# HandyPico.net
KiCad netlist of a schematic drawn in EasyEDA Pro
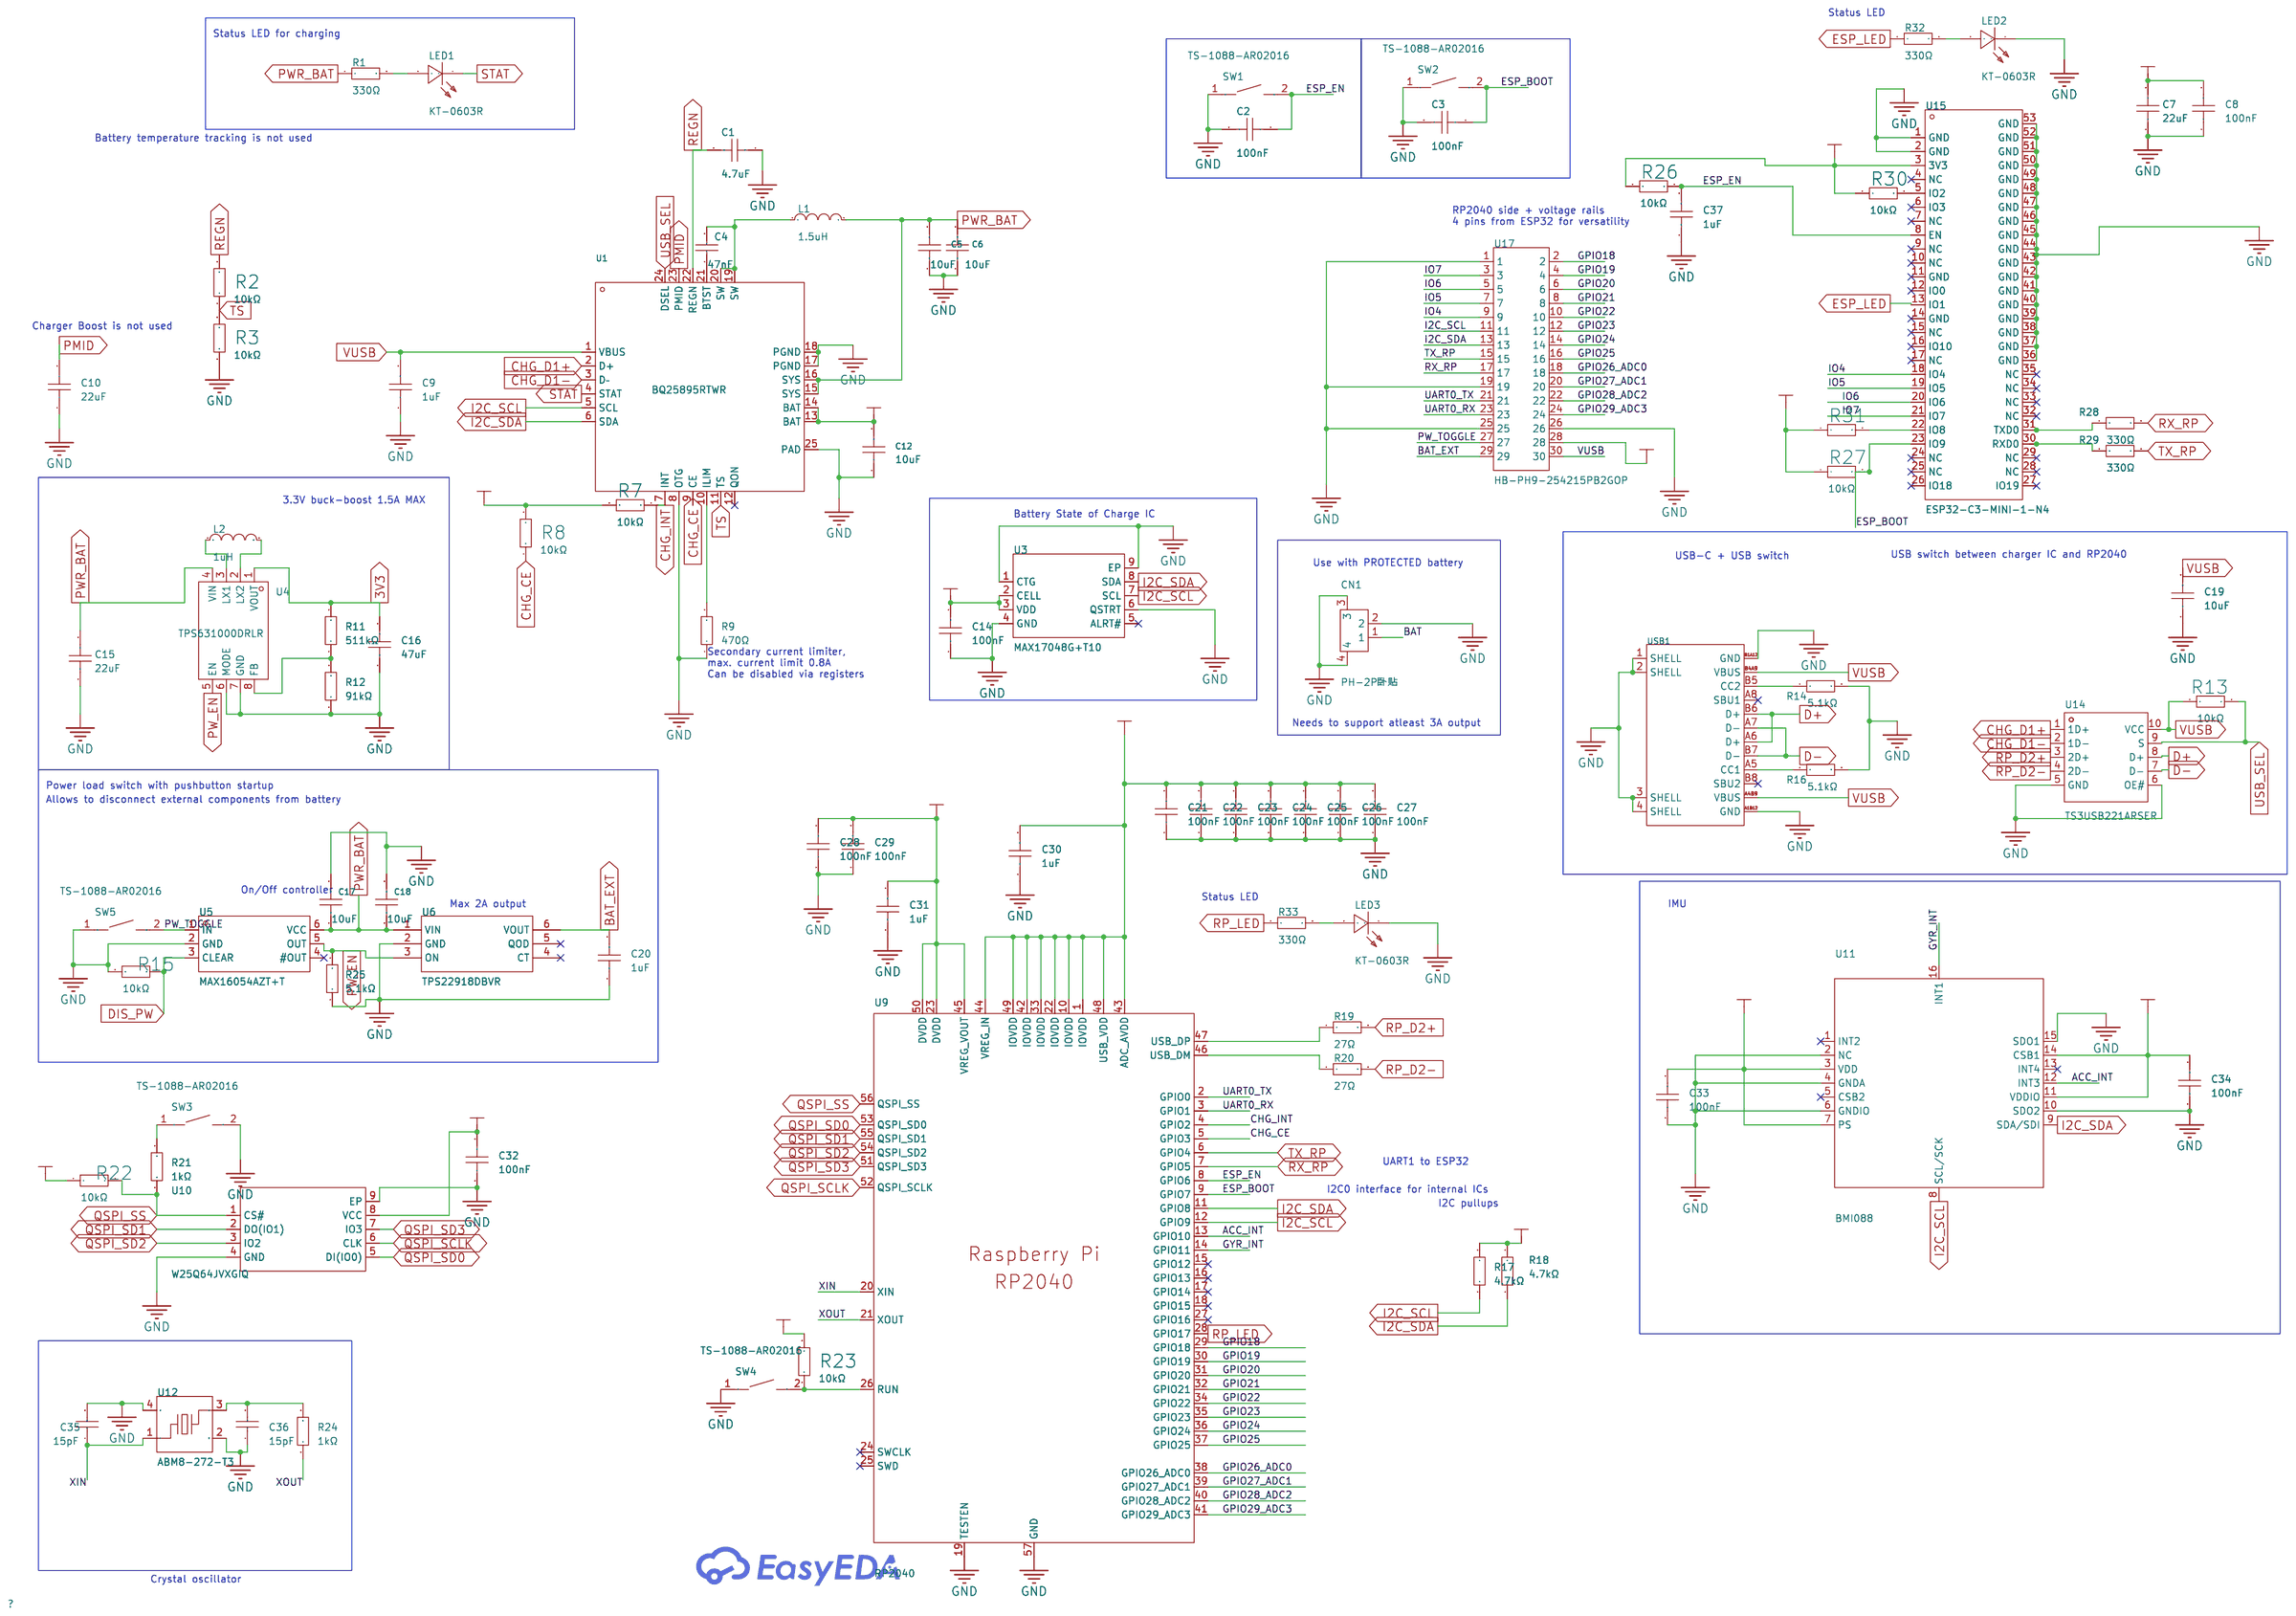
[diagram p0: schematic sheet]

(export (version "E")
  (design (tool "Eeschema 10.0.6"))
  (components
    (comp (ref "C1")
      (value "4.7uF")
      (footprint "easyedapro:C0603")
      (fields
        (field (name "Manufacturer Part") "CL05A475MP5NRNC")
        (field (name "Manufacturer") "SAMSUNG(三星)")
      )
      (libsource (lib "easyedapro") (part "CL10A475KO8NNNC"))
    )
    (comp (ref "C2")
      (value "100nF")
      (footprint "easyedapro:C0603")
      (fields
        (field (name "Manufacturer Part") "CL05B104KO5NNNC")
        (field (name "Manufacturer") "SAMSUNG(三星)")
      )
      (libsource (lib "easyedapro") (part "CC0603KRX7R9BB104"))
    )
    (comp (ref "C3")
      (value "100nF")
      (footprint "easyedapro:C0603")
      (fields
        (field (name "Manufacturer Part") "CL05B104KO5NNNC")
        (field (name "Manufacturer") "SAMSUNG(三星)")
      )
      (libsource (lib "easyedapro") (part "CC0603KRX7R9BB104"))
    )
    (comp (ref "C4")
      (value "47nF")
      (footprint "easyedapro:C0603")
      (fields
        (field (name "Manufacturer Part") "CL10B473KB8NNNC")
        (field (name "Manufacturer") "SAMSUNG(三星)")
      )
      (libsource (lib "easyedapro") (part "CL10B473KB8NNNC"))
    )
    (comp (ref "C5")
      (value "10uF")
      (footprint "easyedapro:C0603")
      (fields
        (field (name "Manufacturer Part") "CL10A106MA8NRNC")
        (field (name "Manufacturer") "SAMSUNG(三星)")
      )
      (libsource (lib "easyedapro") (part "CL10A106MA8NRNC"))
    )
    (comp (ref "C6")
      (value "10uF")
      (footprint "easyedapro:C0603")
      (fields
        (field (name "Manufacturer Part") "CL10A106MA8NRNC")
        (field (name "Manufacturer") "SAMSUNG(三星)")
      )
      (libsource (lib "easyedapro") (part "CL10A106MA8NRNC"))
    )
    (comp (ref "C7")
      (value "22uF")
      (footprint "easyedapro:C0603")
      (fields
        (field (name "Manufacturer Part") "GRM187R61A226ME15D")
        (field (name "Manufacturer") "muRata(村田)")
      )
      (libsource (lib "easyedapro") (part "GRM187R61A226ME15D"))
    )
    (comp (ref "C8")
      (value "100nF")
      (footprint "easyedapro:C0603")
      (fields
        (field (name "Manufacturer Part") "CL05B104KO5NNNC")
        (field (name "Manufacturer") "SAMSUNG(三星)")
      )
      (libsource (lib "easyedapro") (part "CC0603KRX7R9BB104"))
    )
    (comp (ref "C9")
      (value "1uF")
      (footprint "easyedapro:C0603")
      (fields
        (field (name "Manufacturer Part") "CL10A105KB8NNNC")
        (field (name "Manufacturer") "SAMSUNG(三星)")
      )
      (libsource (lib "easyedapro") (part "CL10A105KB8NNNC"))
    )
    (comp (ref "C10")
      (value "22uF")
      (footprint "easyedapro:C0603")
      (fields
        (field (name "Manufacturer Part") "CL10A226MQ8NRNC")
        (field (name "Manufacturer") "SAMSUNG(三星)")
      )
      (libsource (lib "easyedapro") (part "CL10A226MQ8NRNC"))
    )
    (comp (ref "C12")
      (value "10uF")
      (footprint "easyedapro:C0603")
      (fields
        (field (name "Manufacturer Part") "CL10A106MA8NRNC")
        (field (name "Manufacturer") "SAMSUNG(三星)")
      )
      (libsource (lib "easyedapro") (part "CL10A106MA8NRNC"))
    )
    (comp (ref "C14")
      (value "100nF")
      (footprint "easyedapro:C0603")
      (fields
        (field (name "Manufacturer Part") "CL05B104KO5NNNC")
        (field (name "Manufacturer") "SAMSUNG(三星)")
      )
      (libsource (lib "easyedapro") (part "CC0603KRX7R9BB104"))
    )
    (comp (ref "C15")
      (value "22uF")
      (footprint "easyedapro:C0603")
      (fields
        (field (name "Manufacturer Part") "GRM187R61A226ME15D")
        (field (name "Manufacturer") "muRata(村田)")
      )
      (libsource (lib "easyedapro") (part "GRM187R61A226ME15D"))
    )
    (comp (ref "C16")
      (value "47uF")
      (footprint "easyedapro:C0603")
      (fields
        (field (name "Manufacturer Part") "CL10A476MQ8QRNC")
        (field (name "Manufacturer") "SAMSUNG(三星)")
      )
      (libsource (lib "easyedapro") (part "CL10A476MQ8QRNC"))
    )
    (comp (ref "C17")
      (value "10uF")
      (footprint "easyedapro:C0603")
      (fields
        (field (name "Manufacturer Part") "CL10A106MA8NRNC")
        (field (name "Manufacturer") "SAMSUNG(三星)")
      )
      (libsource (lib "easyedapro") (part "CL10A106MA8NRNC"))
    )
    (comp (ref "C18")
      (value "10uF")
      (footprint "easyedapro:C0603")
      (fields
        (field (name "Manufacturer Part") "CL10A106MA8NRNC")
        (field (name "Manufacturer") "SAMSUNG(三星)")
      )
      (libsource (lib "easyedapro") (part "CL10A106MA8NRNC"))
    )
    (comp (ref "C19")
      (value "10uF")
      (footprint "easyedapro:C0603")
      (fields
        (field (name "Manufacturer Part") "CL10A106KP8NNNC")
        (field (name "Manufacturer") "SAMSUNG(三星)")
      )
      (libsource (lib "easyedapro") (part "CL10A106KP8NNNC"))
    )
    (comp (ref "C20")
      (value "1uF")
      (footprint "easyedapro:C0603")
      (fields
        (field (name "Manufacturer Part") "CL10A105KB8NNNC")
        (field (name "Manufacturer") "SAMSUNG(三星)")
      )
      (libsource (lib "easyedapro") (part "CL10A105KB8NNNC"))
    )
    (comp (ref "C21")
      (value "100nF")
      (footprint "easyedapro:C0603")
      (fields
        (field (name "Manufacturer Part") "CL05B104KO5NNNC")
        (field (name "Manufacturer") "SAMSUNG(三星)")
      )
      (libsource (lib "easyedapro") (part "CC0603KRX7R9BB104"))
    )
    (comp (ref "C22")
      (value "100nF")
      (footprint "easyedapro:C0603")
      (fields
        (field (name "Manufacturer Part") "CL05B104KO5NNNC")
        (field (name "Manufacturer") "SAMSUNG(三星)")
      )
      (libsource (lib "easyedapro") (part "CC0603KRX7R9BB104"))
    )
    (comp (ref "C23")
      (value "100nF")
      (footprint "easyedapro:C0603")
      (fields
        (field (name "Manufacturer Part") "CL05B104KO5NNNC")
        (field (name "Manufacturer") "SAMSUNG(三星)")
      )
      (libsource (lib "easyedapro") (part "CC0603KRX7R9BB104"))
    )
    (comp (ref "C24")
      (value "100nF")
      (footprint "easyedapro:C0603")
      (fields
        (field (name "Manufacturer Part") "CL05B104KO5NNNC")
        (field (name "Manufacturer") "SAMSUNG(三星)")
      )
      (libsource (lib "easyedapro") (part "CC0603KRX7R9BB104"))
    )
    (comp (ref "C25")
      (value "100nF")
      (footprint "easyedapro:C0603")
      (fields
        (field (name "Manufacturer Part") "CL05B104KO5NNNC")
        (field (name "Manufacturer") "SAMSUNG(三星)")
      )
      (libsource (lib "easyedapro") (part "CC0603KRX7R9BB104"))
    )
    (comp (ref "C26")
      (value "100nF")
      (footprint "easyedapro:C0603")
      (fields
        (field (name "Manufacturer Part") "CL05B104KO5NNNC")
        (field (name "Manufacturer") "SAMSUNG(三星)")
      )
      (libsource (lib "easyedapro") (part "CC0603KRX7R9BB104"))
    )
    (comp (ref "C27")
      (value "100nF")
      (footprint "easyedapro:C0603")
      (fields
        (field (name "Manufacturer Part") "CL05B104KO5NNNC")
        (field (name "Manufacturer") "SAMSUNG(三星)")
      )
      (libsource (lib "easyedapro") (part "CC0603KRX7R9BB104"))
    )
    (comp (ref "C28")
      (value "100nF")
      (footprint "easyedapro:C0603")
      (fields
        (field (name "Manufacturer Part") "CL05B104KO5NNNC")
        (field (name "Manufacturer") "SAMSUNG(三星)")
      )
      (libsource (lib "easyedapro") (part "CC0603KRX7R9BB104"))
    )
    (comp (ref "C29")
      (value "100nF")
      (footprint "easyedapro:C0603")
      (fields
        (field (name "Manufacturer Part") "CL05B104KO5NNNC")
        (field (name "Manufacturer") "SAMSUNG(三星)")
      )
      (libsource (lib "easyedapro") (part "CC0603KRX7R9BB104"))
    )
    (comp (ref "C30")
      (value "1uF")
      (footprint "easyedapro:C0603")
      (description "Capacitance:1uF Tolerance:±10% Tolerance:±10% Voltage Rating:25V Temperature Coefficient:X5R")
      (fields
        (field (name "Manufacturer Part") "CL05A105KA5NQNC")
        (field (name "Manufacturer") "SAMSUNG(三星)")
      )
      (libsource (lib "easyedapro") (part "CL10A105KB8NNNC"))
    )
    (comp (ref "C31")
      (value "1uF")
      (footprint "easyedapro:C0603")
      (description "Capacitance:1uF Tolerance:±10% Tolerance:±10% Voltage Rating:25V Temperature Coefficient:X5R")
      (fields
        (field (name "Manufacturer Part") "CL05A105KA5NQNC")
        (field (name "Manufacturer") "SAMSUNG(三星)")
      )
      (libsource (lib "easyedapro") (part "CL10A105KB8NNNC"))
    )
    (comp (ref "C32")
      (value "100nF")
      (footprint "easyedapro:C0603")
      (fields
        (field (name "Manufacturer Part") "CL05B104KO5NNNC")
        (field (name "Manufacturer") "SAMSUNG(三星)")
      )
      (libsource (lib "easyedapro") (part "CC0603KRX7R9BB104"))
    )
    (comp (ref "C33")
      (value "100nF")
      (footprint "easyedapro:C0603")
      (fields
        (field (name "Manufacturer Part") "CL05B104KO5NNNC")
        (field (name "Manufacturer") "SAMSUNG(三星)")
      )
      (libsource (lib "easyedapro") (part "CC0603KRX7R9BB104"))
    )
    (comp (ref "C34")
      (value "100nF")
      (footprint "easyedapro:C0603")
      (fields
        (field (name "Manufacturer Part") "CL05B104KO5NNNC")
        (field (name "Manufacturer") "SAMSUNG(三星)")
      )
      (libsource (lib "easyedapro") (part "CC0603KRX7R9BB104"))
    )
    (comp (ref "C35")
      (value "15pF")
      (footprint "easyedapro:C0603")
      (fields
        (field (name "Manufacturer Part") "CL10C150JB8NNNC")
        (field (name "Manufacturer") "SAMSUNG(三星)")
      )
      (libsource (lib "easyedapro") (part "CL10C150JB8NNNC"))
    )
    (comp (ref "C36")
      (value "15pF")
      (footprint "easyedapro:C0603")
      (fields
        (field (name "Manufacturer Part") "CL10C150JB8NNNC")
        (field (name "Manufacturer") "SAMSUNG(三星)")
      )
      (libsource (lib "easyedapro") (part "CL10C150JB8NNNC"))
    )
    (comp (ref "C37")
      (value "1uF")
      (footprint "easyedapro:C0603")
      (description "Capacitance:1uF Tolerance:±10% Tolerance:±10% Voltage Rating:25V Temperature Coefficient:X5R")
      (fields
        (field (name "Manufacturer Part") "CL05A105KA5NQNC")
        (field (name "Manufacturer") "SAMSUNG(三星)")
      )
      (libsource (lib "easyedapro") (part "CL10A105KB8NNNC"))
    )
    (comp (ref "CN1")
      (value "PH-2P卧贴")
      (footprint "easyedapro:CONN-SMD_2P-P2.00_PH2.0-SPWB")
      (fields (field (name "Manufacturer") "BOOMELE(博穆精密)"))
      (libsource (lib "easyedapro") (part "PH2.0-2PWB"))
    )
    (comp (ref "L1")
      (value "1.5uH")
      (footprint "easyedapro:IND-SMD_L4.4-W4.2")
      (fields (field (name "Manufacturer Part") "FXL0420-1R5-M") (field (name "Manufacturer") "cjiang(长江微电)"))
      (libsource (lib "easyedapro") (part "FXL0420-1R5-M"))
    )
    (comp (ref "L2")
      (value "1uH")
      (footprint "easyedapro:L1008")
      (fields
        (field (name "Manufacturer Part") "DFE252012P-1R0M=P2")
        (field (name "Manufacturer") "muRata(村田)")
      )
      (libsource (lib "easyedapro") (part "DFE252012P-1R0M=P2"))
    )
    (comp (ref "LED1")
      (value "KT-0603R")
      (footprint "easyedapro:LED0603-RD")
      (fields (field (name "Manufacturer") "KENTO"))
      (libsource (lib "easyedapro") (part "KT-0603R"))
    )
    (comp (ref "LED2")
      (value "KT-0603R")
      (footprint "easyedapro:LED0603-RD")
      (fields (field (name "Manufacturer") "KENTO"))
      (libsource (lib "easyedapro") (part "KT-0603R"))
    )
    (comp (ref "LED3")
      (value "KT-0603R")
      (footprint "easyedapro:LED0603-RD")
      (fields (field (name "Manufacturer") "KENTO"))
      (libsource (lib "easyedapro") (part "KT-0603R"))
    )
    (comp (ref "R1")
      (value "330Ω")
      (footprint "easyedapro:R0603")
      (fields
        (field (name "Manufacturer Part") "0402WGF3300TCE")
        (field (name "Manufacturer") "UNI-ROYAL(厚声)")
      )
      (libsource (lib "easyedapro") (part "0603WAF2201T5E"))
    )
    (comp (ref "R2")
      (value "10kΩ")
      (footprint "easyedapro:R0603")
      (fields
        (field (name "Manufacturer Part") "0402WGF1002TCE")
        (field (name "Manufacturer") "UNI-ROYAL(厚声)")
      )
      (libsource (lib "easyedapro") (part "0603WAF1002T5E"))
    )
    (comp (ref "R3")
      (value "10kΩ")
      (footprint "easyedapro:R0603")
      (fields
        (field (name "Manufacturer Part") "0402WGF1002TCE")
        (field (name "Manufacturer") "UNI-ROYAL(厚声)")
      )
      (libsource (lib "easyedapro") (part "0603WAF1002T5E"))
    )
    (comp (ref "R7")
      (value "10kΩ")
      (footprint "easyedapro:R0603")
      (fields
        (field (name "Manufacturer Part") "0402WGF1002TCE")
        (field (name "Manufacturer") "UNI-ROYAL(厚声)")
      )
      (libsource (lib "easyedapro") (part "0603WAF1002T5E"))
    )
    (comp (ref "R8")
      (value "10kΩ")
      (footprint "easyedapro:R0603")
      (fields
        (field (name "Manufacturer Part") "0402WGF1002TCE")
        (field (name "Manufacturer") "UNI-ROYAL(厚声)")
      )
      (libsource (lib "easyedapro") (part "0603WAF1002T5E"))
    )
    (comp (ref "R9")
      (value "470Ω")
      (footprint "easyedapro:R0603")
      (fields
        (field (name "Manufacturer Part") "0402WGF4700TCE")
        (field (name "Manufacturer") "UNI-ROYAL(厚声)")
      )
      (libsource (lib "easyedapro") (part "0603WAF4700T5E"))
    )
    (comp (ref "R11")
      (value "511kΩ")
      (footprint "easyedapro:R0603")
      (fields
        (field (name "Manufacturer Part") "0402WGF5113TCE")
        (field (name "Manufacturer") "UNI-ROYAL(厚声)")
      )
      (libsource (lib "easyedapro") (part "0603WAF5113T5E"))
    )
    (comp (ref "R12")
      (value "91kΩ")
      (footprint "easyedapro:R0603")
      (fields
        (field (name "Manufacturer Part") "0402WGF9102TCE")
        (field (name "Manufacturer") "UNI-ROYAL(厚声)")
      )
      (libsource (lib "easyedapro") (part "0603WAF9102T5E"))
    )
    (comp (ref "R13")
      (value "10kΩ")
      (footprint "easyedapro:R0603")
      (fields
        (field (name "Manufacturer Part") "0402WGF1002TCE")
        (field (name "Manufacturer") "UNI-ROYAL(厚声)")
      )
      (libsource (lib "easyedapro") (part "0603WAF1002T5E"))
    )
    (comp (ref "R14")
      (value "5.1kΩ")
      (footprint "easyedapro:R0603")
      (fields
        (field (name "Manufacturer Part") "0402WGF5101TCE")
        (field (name "Manufacturer") "UNI-ROYAL(厚声)")
      )
      (libsource (lib "easyedapro") (part "0603WAF5101T5E"))
    )
    (comp (ref "R15")
      (value "10kΩ")
      (footprint "easyedapro:R0603")
      (fields
        (field (name "Manufacturer Part") "0402WGF1002TCE")
        (field (name "Manufacturer") "UNI-ROYAL(厚声)")
      )
      (libsource (lib "easyedapro") (part "0603WAF1002T5E"))
    )
    (comp (ref "R16")
      (value "5.1kΩ")
      (footprint "easyedapro:R0603")
      (fields
        (field (name "Manufacturer Part") "0402WGF5101TCE")
        (field (name "Manufacturer") "UNI-ROYAL(厚声)")
      )
      (libsource (lib "easyedapro") (part "0603WAF5101T5E"))
    )
    (comp (ref "R17")
      (value "4.7kΩ")
      (footprint "easyedapro:R0603")
      (fields
        (field (name "Manufacturer Part") "0402WGF4701TCE")
        (field (name "Manufacturer") "UNI-ROYAL(厚声)")
      )
      (libsource (lib "easyedapro") (part "0603WAF4701T5E"))
    )
    (comp (ref "R18")
      (value "4.7kΩ")
      (footprint "easyedapro:R0603")
      (fields
        (field (name "Manufacturer Part") "0402WGF4701TCE")
        (field (name "Manufacturer") "UNI-ROYAL(厚声)")
      )
      (libsource (lib "easyedapro") (part "0603WAF4701T5E"))
    )
    (comp (ref "R19")
      (value "27Ω")
      (footprint "easyedapro:R0603")
      (fields
        (field (name "Manufacturer Part") "0603WAF270JT5E")
        (field (name "Manufacturer") "UNI-ROYAL(厚声)")
      )
      (libsource (lib "easyedapro") (part "0603WAF270JT5E"))
    )
    (comp (ref "R20")
      (value "27Ω")
      (footprint "easyedapro:R0603")
      (fields
        (field (name "Manufacturer Part") "0603WAF270JT5E")
        (field (name "Manufacturer") "UNI-ROYAL(厚声)")
      )
      (libsource (lib "easyedapro") (part "0603WAF270JT5E"))
    )
    (comp (ref "R21")
      (value "1kΩ")
      (footprint "easyedapro:R0603")
      (fields
        (field (name "Manufacturer Part") "0402WGF1001TCE")
        (field (name "Manufacturer") "UNI-ROYAL(厚声)")
      )
      (libsource (lib "easyedapro") (part "0603WAF1001T5E"))
    )
    (comp (ref "R22")
      (value "10kΩ")
      (footprint "easyedapro:R0603")
      (fields
        (field (name "Manufacturer Part") "0402WGF1002TCE")
        (field (name "Manufacturer") "UNI-ROYAL(厚声)")
      )
      (libsource (lib "easyedapro") (part "0603WAF1002T5E"))
    )
    (comp (ref "R23")
      (value "10kΩ")
      (footprint "easyedapro:R0603")
      (fields
        (field (name "Manufacturer Part") "0402WGF1002TCE")
        (field (name "Manufacturer") "UNI-ROYAL(厚声)")
      )
      (libsource (lib "easyedapro") (part "0603WAF1002T5E"))
    )
    (comp (ref "R24")
      (value "1kΩ")
      (footprint "easyedapro:R0603")
      (fields
        (field (name "Manufacturer Part") "0402WGF1001TCE")
        (field (name "Manufacturer") "UNI-ROYAL(厚声)")
      )
      (libsource (lib "easyedapro") (part "0603WAF1001T5E"))
    )
    (comp (ref "R25")
      (value "5.1kΩ")
      (footprint "easyedapro:R0603")
      (fields
        (field (name "Manufacturer Part") "0402WGF5101TCE")
        (field (name "Manufacturer") "UNI-ROYAL(厚声)")
      )
      (libsource (lib "easyedapro") (part "0603WAF5101T5E"))
    )
    (comp (ref "R26")
      (value "10kΩ")
      (footprint "easyedapro:R0603")
      (fields
        (field (name "Manufacturer Part") "0402WGF1002TCE")
        (field (name "Manufacturer") "UNI-ROYAL(厚声)")
      )
      (libsource (lib "easyedapro") (part "0603WAF1002T5E"))
    )
    (comp (ref "R27")
      (value "10kΩ")
      (footprint "easyedapro:R0603")
      (fields
        (field (name "Manufacturer Part") "0402WGF1002TCE")
        (field (name "Manufacturer") "UNI-ROYAL(厚声)")
      )
      (libsource (lib "easyedapro") (part "0603WAF1002T5E"))
    )
    (comp (ref "R28")
      (value "330Ω")
      (footprint "easyedapro:R0603")
      (fields
        (field (name "Manufacturer Part") "0402WGF3300TCE")
        (field (name "Manufacturer") "UNI-ROYAL(厚声)")
      )
      (libsource (lib "easyedapro") (part "0603WAF3300T5E"))
    )
    (comp (ref "R29")
      (value "330Ω")
      (footprint "easyedapro:R0603")
      (fields
        (field (name "Manufacturer Part") "0402WGF3300TCE")
        (field (name "Manufacturer") "UNI-ROYAL(厚声)")
      )
      (libsource (lib "easyedapro") (part "0603WAF3300T5E"))
    )
    (comp (ref "R30")
      (value "10kΩ")
      (footprint "easyedapro:R0603")
      (fields
        (field (name "Manufacturer Part") "0402WGF1002TCE")
        (field (name "Manufacturer") "UNI-ROYAL(厚声)")
      )
      (libsource (lib "easyedapro") (part "0603WAF1002T5E"))
    )
    (comp (ref "R31")
      (value "10kΩ")
      (footprint "easyedapro:R0603")
      (fields
        (field (name "Manufacturer Part") "0402WGF1002TCE")
        (field (name "Manufacturer") "UNI-ROYAL(厚声)")
      )
      (libsource (lib "easyedapro") (part "0603WAF1002T5E"))
    )
    (comp (ref "R32")
      (value "330Ω")
      (footprint "easyedapro:R0603")
      (fields
        (field (name "Manufacturer Part") "0402WGF3300TCE")
        (field (name "Manufacturer") "UNI-ROYAL(厚声)")
      )
      (libsource (lib "easyedapro") (part "0603WAF2201T5E"))
    )
    (comp (ref "R33")
      (value "330Ω")
      (footprint "easyedapro:R0603")
      (fields
        (field (name "Manufacturer Part") "0402WGF3300TCE")
        (field (name "Manufacturer") "UNI-ROYAL(厚声)")
      )
      (libsource (lib "easyedapro") (part "0603WAF2201T5E"))
    )
    (comp (ref "SW1")
      (value "TS-1088-AR02016")
      (footprint "easyedapro:SW-SMD_L3.9-W3.0-P4.45")
      (fields (field (name "Manufacturer") "XUNPU(讯普)"))
      (libsource (lib "easyedapro") (part "TS-1088-AR02016"))
    )
    (comp (ref "SW2")
      (value "TS-1088-AR02016")
      (footprint "easyedapro:SW-SMD_L3.9-W3.0-P4.45")
      (fields (field (name "Manufacturer") "XUNPU(讯普)"))
      (libsource (lib "easyedapro") (part "TS-1088-AR02016"))
    )
    (comp (ref "SW3")
      (value "TS-1088-AR02016")
      (footprint "easyedapro:SW-SMD_L3.9-W3.0-P4.45")
      (fields (field (name "Manufacturer") "XUNPU(讯普)"))
      (libsource (lib "easyedapro") (part "TS-1088-AR02016"))
    )
    (comp (ref "SW4")
      (value "TS-1088-AR02016")
      (footprint "easyedapro:SW-SMD_L3.9-W3.0-P4.45")
      (fields (field (name "Manufacturer") "XUNPU(讯普)"))
      (libsource (lib "easyedapro") (part "TS-1088-AR02016"))
    )
    (comp (ref "SW5")
      (value "TS-1088-AR02016")
      (footprint "easyedapro:SW-SMD_L3.9-W3.0-P4.45")
      (fields (field (name "Manufacturer") "XUNPU(讯普)"))
      (libsource (lib "easyedapro") (part "TS-1088-AR02016"))
    )
    (comp (ref "U1")
      (value "BQ25895RTWR")
      (footprint "easyedapro:QFN-24_L4.0-W4.0-P0.50-TL-EP2.7")
      (fields (field (name "Manufacturer") "TI(德州仪器)"))
      (libsource (lib "easyedapro") (part "BQ25895RTWR"))
    )
    (comp (ref "U3")
      (value "MAX17048G+T10")
      (footprint "easyedapro:TDFN-8_L2.0-W2.0-P0.50-BL-EP1.2")
      (fields (field (name "Manufacturer") "ADI(亚德诺)/MAXIM(美信)"))
      (libsource (lib "easyedapro") (part "MAX17048G+T10"))
    )
    (comp (ref "U4")
      (value "TPS631000DRLR")
      (footprint "easyedapro:SOT-583-8_L2.1-W1.2-P0.50-LS1.6-BL")
      (fields (field (name "Manufacturer") "TI(德州仪器)"))
      (libsource (lib "easyedapro") (part "TPS631000DRLR"))
    )
    (comp (ref "U5")
      (value "MAX16054AZT+T")
      (footprint "easyedapro:TSOT-23-6_L2.9-W1.6-P0.95-LS2.8-TL")
      (fields (field (name "Manufacturer") "ADI(亚德诺)"))
      (libsource (lib "easyedapro") (part "MAX16054AZT+T"))
    )
    (comp (ref "U6")
      (value "TPS22918DBVR")
      (footprint "easyedapro:SOT-23-6_L2.9-W1.6-P0.95-LS2.8-BR")
      (fields (field (name "Manufacturer") "TI(德州仪器)"))
      (libsource (lib "easyedapro") (part "TPS22918DBVR"))
    )
    (comp (ref "U9")
      (value "RP2040")
      (footprint "easyedapro:LQFN-56_L7.0-W7.0-P0.4-EP")
      (description "CPU Core:- CPU Maximum Speed:133MHz Number of I/O:30 ADC (Bit):12bit Applications:-")
      (fields (field (name "Manufacturer") "Raspberry Pi(树莓派)"))
      (libsource (lib "easyedapro") (part "RP2040"))
    )
    (comp (ref "U10")
      (value "W25Q64JVXGIQ")
      (footprint "easyedapro:XSON-8_L4.0-W4.0-P0.80-TL-EP")
      (fields (field (name "Manufacturer") "Winbond(华邦)"))
      (libsource (lib "easyedapro") (part "W25Q64JVXGIQ"))
    )
    (comp (ref "U11")
      (value "BMI088")
      (footprint "easyedapro:LGA-16_L4.5-W3.0-P0.50-BL")
      (description "Sensor Type:加速度计陀螺仪 Operating Temperature:-40°C~+85°C Operating Temperature:-40°C~+85°C")
      (fields (field (name "Manufacturer") "Bosch(博世)"))
      (libsource (lib "easyedapro") (part "BMI088"))
    )
    (comp (ref "U12")
      (value "ABM8-272-T3")
      (footprint "easyedapro:CRYSTAL-SMD_4P-L3.2-W2.5-BL")
      (fields (field (name "Manufacturer") "ABRACON"))
      (libsource (lib "easyedapro") (part "ABM8-272-T3_C20625731"))
    )
    (comp (ref "U14")
      (value "TS3USB221ARSER")
      (footprint "easyedapro:UQFN-10_L2.0-W1.5-P0.50-BL")
      (fields (field (name "Manufacturer") "TI(德州仪器)"))
      (libsource (lib "easyedapro") (part "TS3USB221ARSER"))
    )
    (comp (ref "U15")
      (value "ESP32-C3-MINI-1-N4")
      (footprint "easyedapro:WIFIM-SMD_ESP32-C3-MINI-1")
      (fields (field (name "Manufacturer") "ESPRESSIF(乐鑫)"))
      (libsource (lib "easyedapro") (part "ESP32-C3-MINI-1-N4"))
    )
    (comp (ref "U17")
      (value "HB-PH9-254215PB2GOP")
      (footprint "easyedapro:HDR-SMD_30P-P2.54-V-M-R2-C15-S7.4")
      (fields (field (name "Manufacturer") "HANBO(汉博)"))
      (libsource (lib "easyedapro") (part "HB-PH9-254215PB2GOP"))
    )
    (comp (ref "USB1")
      (value "HC-TYPE-C-16P-01A-R")
      (footprint "easyedapro:USB-C-SMD_G-SWITCH_GT-USB-7010EN")
      (fields (field (name "Manufacturer") "HCTL(华灿天禄)"))
      (libsource (lib "easyedapro") (part "HC-TYPE-C-16P-01A-R"))
    )
  )
  (nets
    (net (code "1") (name "/ACC_INT") (class "Default")
      (node (ref "U11") (pin "12") (pinfunction "INT3_12") (pintype "unspecified"))
      (node (ref "U9") (pin "13") (pinfunction "GPIO10_13") (pintype "bidirectional"))
    )
    (net (code "2") (name "/ESP_BOOT") (class "Default")
      (node (ref "C3") (pin "1") (pinfunction "1_1") (pintype "unspecified"))
      (node (ref "R27") (pin "2") (pinfunction "2_2") (pintype "input"))
      (node (ref "SW2") (pin "2") (pinfunction "2_2") (pintype "unspecified"))
      (node (ref "U15") (pin "23") (pinfunction "IO9_23") (pintype "unspecified"))
      (node (ref "U9") (pin "9") (pinfunction "GPIO7_9") (pintype "bidirectional"))
    )
    (net (code "3") (name "/ESP_EN") (class "Default")
      (node (ref "C2") (pin "1") (pinfunction "1_1") (pintype "unspecified"))
      (node (ref "C37") (pin "2") (pinfunction "2_2") (pintype "unspecified"))
      (node (ref "R26") (pin "1") (pinfunction "1_1") (pintype "input"))
      (node (ref "SW1") (pin "2") (pinfunction "2_2") (pintype "unspecified"))
      (node (ref "U15") (pin "8") (pinfunction "EN_8") (pintype "unspecified"))
      (node (ref "U9") (pin "8") (pinfunction "GPIO6_8") (pintype "bidirectional"))
    )
    (net (code "4") (name "/GPIO18") (class "Default")
      (node (ref "U17") (pin "2") (pinfunction "2_2") (pintype "unspecified"))
      (node (ref "U9") (pin "29") (pinfunction "GPIO18_29") (pintype "bidirectional"))
    )
    (net (code "5") (name "/GPIO19") (class "Default")
      (node (ref "U17") (pin "4") (pinfunction "4_4") (pintype "unspecified"))
      (node (ref "U9") (pin "30") (pinfunction "GPIO19_30") (pintype "bidirectional"))
    )
    (net (code "6") (name "/GPIO20") (class "Default")
      (node (ref "U17") (pin "6") (pinfunction "6_6") (pintype "unspecified"))
      (node (ref "U9") (pin "31") (pinfunction "GPIO20_31") (pintype "bidirectional"))
    )
    (net (code "7") (name "/GPIO21") (class "Default")
      (node (ref "U17") (pin "8") (pinfunction "8_8") (pintype "unspecified"))
      (node (ref "U9") (pin "32") (pinfunction "GPIO21_32") (pintype "bidirectional"))
    )
    (net (code "8") (name "/GPIO22") (class "Default")
      (node (ref "U17") (pin "10") (pinfunction "10_10") (pintype "unspecified"))
      (node (ref "U9") (pin "34") (pinfunction "GPIO22_34") (pintype "bidirectional"))
    )
    (net (code "9") (name "/GPIO23") (class "Default")
      (node (ref "U17") (pin "12") (pinfunction "12_12") (pintype "unspecified"))
      (node (ref "U9") (pin "35") (pinfunction "GPIO23_35") (pintype "bidirectional"))
    )
    (net (code "10") (name "/GPIO24") (class "Default")
      (node (ref "U17") (pin "14") (pinfunction "14_14") (pintype "unspecified"))
      (node (ref "U9") (pin "36") (pinfunction "GPIO24_36") (pintype "bidirectional"))
    )
    (net (code "11") (name "/GPIO25") (class "Default")
      (node (ref "U17") (pin "16") (pinfunction "16_16") (pintype "unspecified"))
      (node (ref "U9") (pin "37") (pinfunction "GPIO25_37") (pintype "bidirectional"))
    )
    (net (code "12") (name "/GPIO26_ADC0") (class "Default")
      (node (ref "U17") (pin "18") (pinfunction "18_18") (pintype "unspecified"))
      (node (ref "U9") (pin "38") (pinfunction "GPIO26_ADC0_38") (pintype "bidirectional"))
    )
    (net (code "13") (name "/GPIO27_ADC1") (class "Default")
      (node (ref "U17") (pin "20") (pinfunction "20_20") (pintype "unspecified"))
      (node (ref "U9") (pin "39") (pinfunction "GPIO27_ADC1_39") (pintype "bidirectional"))
    )
    (net (code "14") (name "/GPIO28_ADC2") (class "Default")
      (node (ref "U17") (pin "22") (pinfunction "22_22") (pintype "unspecified"))
      (node (ref "U9") (pin "40") (pinfunction "GPIO28_ADC2_40") (pintype "bidirectional"))
    )
    (net (code "15") (name "/GPIO29_ADC3") (class "Default")
      (node (ref "U17") (pin "24") (pinfunction "24_24") (pintype "unspecified"))
      (node (ref "U9") (pin "41") (pinfunction "GPIO29_ADC3_41") (pintype "bidirectional"))
    )
    (net (code "16") (name "/GYR_INT") (class "Default")
      (node (ref "U11") (pin "16") (pinfunction "INT1_16") (pintype "unspecified"))
      (node (ref "U9") (pin "14") (pinfunction "GPIO11_14") (pintype "bidirectional"))
    )
    (net (code "17") (name "/IO4") (class "Default")
      (node (ref "U15") (pin "18") (pinfunction "IO4_18") (pintype "unspecified"))
      (node (ref "U17") (pin "9") (pinfunction "9_9") (pintype "unspecified"))
    )
    (net (code "18") (name "/IO5") (class "Default")
      (node (ref "U15") (pin "19") (pinfunction "IO5_19") (pintype "unspecified"))
      (node (ref "U17") (pin "7") (pinfunction "7_7") (pintype "unspecified"))
    )
    (net (code "19") (name "/IO6") (class "Default")
      (node (ref "U15") (pin "20") (pinfunction "IO6_20") (pintype "unspecified"))
      (node (ref "U17") (pin "5") (pinfunction "5_5") (pintype "unspecified"))
    )
    (net (code "20") (name "/IO7") (class "Default")
      (node (ref "U15") (pin "21") (pinfunction "IO7_21") (pintype "unspecified"))
      (node (ref "U17") (pin "3") (pinfunction "3_3") (pintype "unspecified"))
    )
    (net (code "21") (name "/PW_TOGGLE") (class "Default")
      (node (ref "SW5") (pin "2") (pinfunction "2_2") (pintype "unspecified"))
      (node (ref "U17") (pin "27") (pinfunction "27_27") (pintype "unspecified"))
      (node (ref "U5") (pin "1") (pinfunction "IN_1") (pintype "unspecified"))
    )
    (net (code "22") (name "/UART0_RX") (class "Default")
      (node (ref "U17") (pin "23") (pinfunction "23_23") (pintype "unspecified"))
      (node (ref "U9") (pin "3") (pinfunction "GPIO1_3") (pintype "bidirectional"))
    )
    (net (code "23") (name "/UART0_TX") (class "Default")
      (node (ref "U17") (pin "21") (pinfunction "21_21") (pintype "unspecified"))
      (node (ref "U9") (pin "2") (pinfunction "GPIO0_2") (pintype "bidirectional"))
    )
    (net (code "24") (name "/XIN") (class "Default")
      (node (ref "C35") (pin "1") (pinfunction "1_1") (pintype "input"))
      (node (ref "U12") (pin "1") (pinfunction "1_1") (pintype "input"))
      (node (ref "U9") (pin "20") (pinfunction "XIN_20") (pintype "input"))
    )
    (net (code "25") (name "/XOUT") (class "Default")
      (node (ref "R24") (pin "1") (pinfunction "1_1") (pintype "input"))
      (node (ref "U9") (pin "21") (pinfunction "XOUT_21") (pintype "unspecified"))
    )
    (net (code "26") (name "1V1") (class "Default")
      (node (ref "C28") (pin "2") (pinfunction "2_2") (pintype "unspecified"))
      (node (ref "C29") (pin "2") (pinfunction "2_2") (pintype "unspecified"))
      (node (ref "C31") (pin "2") (pinfunction "2_2") (pintype "unspecified"))
      (node (ref "U9") (pin "23") (pinfunction "DVDD_23") (pintype "bidirectional"))
      (node (ref "U9") (pin "45") (pinfunction "VREG_VOUT_45") (pintype "bidirectional"))
      (node (ref "U9") (pin "50") (pinfunction "DVDD_50") (pintype "bidirectional"))
    )
    (net (code "27") (name "3V3") (class "Default")
      (node (ref "C16") (pin "2") (pinfunction "2_2") (pintype "unspecified"))
      (node (ref "C21") (pin "2") (pinfunction "2_2") (pintype "unspecified"))
      (node (ref "C22") (pin "2") (pinfunction "2_2") (pintype "unspecified"))
      (node (ref "C23") (pin "2") (pinfunction "2_2") (pintype "unspecified"))
      (node (ref "C24") (pin "2") (pinfunction "2_2") (pintype "unspecified"))
      (node (ref "C25") (pin "2") (pinfunction "2_2") (pintype "unspecified"))
      (node (ref "C26") (pin "2") (pinfunction "2_2") (pintype "unspecified"))
      (node (ref "C27") (pin "2") (pinfunction "2_2") (pintype "unspecified"))
      (node (ref "C30") (pin "2") (pinfunction "2_2") (pintype "unspecified"))
      (node (ref "C32") (pin "2") (pinfunction "2_2") (pintype "unspecified"))
      (node (ref "C33") (pin "2") (pinfunction "2_2") (pintype "unspecified"))
      (node (ref "C34") (pin "2") (pinfunction "2_2") (pintype "unspecified"))
      (node (ref "C7") (pin "2") (pinfunction "2_2") (pintype "unspecified"))
      (node (ref "C8") (pin "2") (pinfunction "2_2") (pintype "unspecified"))
      (node (ref "R11") (pin "2") (pinfunction "2_2") (pintype "input"))
      (node (ref "R17") (pin "2") (pinfunction "2_2") (pintype "input"))
      (node (ref "R18") (pin "2") (pinfunction "2_2") (pintype "input"))
      (node (ref "R22") (pin "1") (pinfunction "1_1") (pintype "input"))
      (node (ref "R23") (pin "2") (pinfunction "2_2") (pintype "input"))
      (node (ref "R26") (pin "2") (pinfunction "2_2") (pintype "input"))
      (node (ref "R27") (pin "1") (pinfunction "1_1") (pintype "input"))
      (node (ref "R30") (pin "1") (pinfunction "1_1") (pintype "input"))
      (node (ref "R31") (pin "1") (pinfunction "1_1") (pintype "input"))
      (node (ref "R7") (pin "2") (pinfunction "2_2") (pintype "input"))
      (node (ref "R8") (pin "2") (pinfunction "2_2") (pintype "input"))
      (node (ref "U10") (pin "8") (pinfunction "VCC_8") (pintype "unspecified"))
      (node (ref "U11") (pin "11") (pinfunction "VDDIO_11") (pintype "unspecified"))
      (node (ref "U11") (pin "14") (pinfunction "CSB1_14") (pintype "unspecified"))
      (node (ref "U11") (pin "3") (pinfunction "VDD_3") (pintype "unspecified"))
      (node (ref "U11") (pin "7") (pinfunction "PS_7") (pintype "unspecified"))
      (node (ref "U15") (pin "3") (pinfunction "3V3_3") (pintype "unspecified"))
      (node (ref "U17") (pin "28") (pinfunction "28_28") (pintype "unspecified"))
      (node (ref "U4") (pin "1") (pinfunction "VOUT_1") (pintype "unspecified"))
      (node (ref "U9") (pin "1") (pinfunction "IOVDD_1") (pintype "bidirectional"))
      (node (ref "U9") (pin "10") (pinfunction "IOVDD_10") (pintype "bidirectional"))
      (node (ref "U9") (pin "22") (pinfunction "IOVDD_22") (pintype "bidirectional"))
      (node (ref "U9") (pin "33") (pinfunction "IOVDD_33") (pintype "bidirectional"))
      (node (ref "U9") (pin "42") (pinfunction "IOVDD_42") (pintype "bidirectional"))
      (node (ref "U9") (pin "43") (pinfunction "ADC_AVDD_43") (pintype "bidirectional"))
      (node (ref "U9") (pin "44") (pinfunction "VREG_IN_44") (pintype "bidirectional"))
      (node (ref "U9") (pin "48") (pinfunction "USB_VDD_48") (pintype "bidirectional"))
      (node (ref "U9") (pin "49") (pinfunction "IOVDD_49") (pintype "bidirectional"))
    )
    (net (code "28") (name "BAT") (class "Default")
      (node (ref "C12") (pin "2") (pinfunction "2_2") (pintype "input"))
      (node (ref "C14") (pin "2") (pinfunction "2_2") (pintype "unspecified"))
      (node (ref "CN1") (pin "1") (pinfunction "1_1") (pintype "unspecified"))
      (node (ref "U1") (pin "13") (pinfunction "BAT_13") (pintype "input"))
      (node (ref "U1") (pin "14") (pinfunction "BAT_14") (pintype "input"))
      (node (ref "U3") (pin "2") (pinfunction "CELL_2") (pintype "unspecified"))
      (node (ref "U3") (pin "3") (pinfunction "VDD_3") (pintype "unspecified"))
    )
    (net (code "29") (name "BAT_EXT") (class "Default")
      (node (ref "C20") (pin "2") (pinfunction "2_2") (pintype "unspecified"))
      (node (ref "U17") (pin "29") (pinfunction "29_29") (pintype "unspecified"))
      (node (ref "U6") (pin "6") (pinfunction "VOUT_6") (pintype "unspecified"))
    )
    (net (code "30") (name "CHG_CE") (class "Default")
      (node (ref "R8") (pin "1") (pinfunction "1_1") (pintype "input"))
      (node (ref "U1") (pin "9") (pinfunction "CE_9") (pintype "input"))
      (node (ref "U9") (pin "5") (pinfunction "GPIO3_5") (pintype "bidirectional"))
    )
    (net (code "31") (name "CHG_D1+") (class "Default")
      (node (ref "U1") (pin "2") (pinfunction "D+_2") (pintype "input"))
      (node (ref "U14") (pin "1") (pinfunction "1D+_1") (pintype "unspecified"))
    )
    (net (code "32") (name "CHG_D1-") (class "Default")
      (node (ref "U1") (pin "3") (pinfunction "D–_3") (pintype "input"))
      (node (ref "U14") (pin "2") (pinfunction "1D-_2") (pintype "unspecified"))
    )
    (net (code "33") (name "CHG_INT") (class "Default")
      (node (ref "R7") (pin "1") (pinfunction "1_1") (pintype "input"))
      (node (ref "U1") (pin "7") (pinfunction "INT_7") (pintype "input"))
      (node (ref "U9") (pin "4") (pinfunction "GPIO2_4") (pintype "bidirectional"))
    )
    (net (code "34") (name "D+") (class "Default")
      (node (ref "U14") (pin "8") (pinfunction "D+_8") (pintype "unspecified"))
      (node (ref "USB1") (pin "A6") (pinfunction "D+_A6") (pintype "unspecified"))
      (node (ref "USB1") (pin "B6") (pinfunction "D+_B6") (pintype "unspecified"))
    )
    (net (code "35") (name "D-") (class "Default")
      (node (ref "U14") (pin "7") (pinfunction "D-_7") (pintype "unspecified"))
      (node (ref "USB1") (pin "A7") (pinfunction "D-_A7") (pintype "unspecified"))
      (node (ref "USB1") (pin "B7") (pinfunction "D-_B7") (pintype "unspecified"))
    )
    (net (code "36") (name "DIS_PW") (class "Default")
      (node (ref "R15") (pin "2") (pinfunction "2_2") (pintype "input"))
      (node (ref "U5") (pin "3") (pinfunction "CLEAR_3") (pintype "unspecified"))
    )
    (net (code "37") (name "ESP_LED") (class "Default")
      (node (ref "R32") (pin "1") (pinfunction "1_1") (pintype "input"))
      (node (ref "U15") (pin "13") (pinfunction "IO1_13") (pintype "unspecified"))
    )
    (net (code "38") (name "GND") (class "Default")
      (node (ref "C1") (pin "1") (pinfunction "1_1") (pintype "unspecified"))
      (node (ref "C10") (pin "1") (pinfunction "1_1") (pintype "unspecified"))
      (node (ref "C12") (pin "1") (pinfunction "1_1") (pintype "input"))
      (node (ref "C14") (pin "1") (pinfunction "1_1") (pintype "unspecified"))
      (node (ref "C15") (pin "1") (pinfunction "1_1") (pintype "unspecified"))
      (node (ref "C16") (pin "1") (pinfunction "1_1") (pintype "unspecified"))
      (node (ref "C17") (pin "2") (pinfunction "2_2") (pintype "input"))
      (node (ref "C18") (pin "2") (pinfunction "2_2") (pintype "input"))
      (node (ref "C19") (pin "1") (pinfunction "1_1") (pintype "unspecified"))
      (node (ref "C2") (pin "2") (pinfunction "2_2") (pintype "unspecified"))
      (node (ref "C20") (pin "1") (pinfunction "1_1") (pintype "unspecified"))
      (node (ref "C21") (pin "1") (pinfunction "1_1") (pintype "unspecified"))
      (node (ref "C22") (pin "1") (pinfunction "1_1") (pintype "unspecified"))
      (node (ref "C23") (pin "1") (pinfunction "1_1") (pintype "unspecified"))
      (node (ref "C24") (pin "1") (pinfunction "1_1") (pintype "unspecified"))
      (node (ref "C25") (pin "1") (pinfunction "1_1") (pintype "unspecified"))
      (node (ref "C26") (pin "1") (pinfunction "1_1") (pintype "unspecified"))
      (node (ref "C27") (pin "1") (pinfunction "1_1") (pintype "unspecified"))
      (node (ref "C28") (pin "1") (pinfunction "1_1") (pintype "unspecified"))
      (node (ref "C29") (pin "1") (pinfunction "1_1") (pintype "unspecified"))
      (node (ref "C3") (pin "2") (pinfunction "2_2") (pintype "unspecified"))
      (node (ref "C30") (pin "1") (pinfunction "1_1") (pintype "unspecified"))
      (node (ref "C31") (pin "1") (pinfunction "1_1") (pintype "unspecified"))
      (node (ref "C32") (pin "1") (pinfunction "1_1") (pintype "unspecified"))
      (node (ref "C33") (pin "1") (pinfunction "1_1") (pintype "unspecified"))
      (node (ref "C34") (pin "1") (pinfunction "1_1") (pintype "unspecified"))
      (node (ref "C35") (pin "2") (pinfunction "2_2") (pintype "input"))
      (node (ref "C36") (pin "1") (pinfunction "1_1") (pintype "input"))
      (node (ref "C37") (pin "1") (pinfunction "1_1") (pintype "unspecified"))
      (node (ref "C5") (pin "1") (pinfunction "1_1") (pintype "input"))
      (node (ref "C6") (pin "1") (pinfunction "1_1") (pintype "input"))
      (node (ref "C7") (pin "1") (pinfunction "1_1") (pintype "unspecified"))
      (node (ref "C8") (pin "1") (pinfunction "1_1") (pintype "unspecified"))
      (node (ref "C9") (pin "1") (pinfunction "1_1") (pintype "unspecified"))
      (node (ref "CN1") (pin "2") (pinfunction "2_2") (pintype "unspecified"))
      (node (ref "CN1") (pin "3") (pinfunction "3_3") (pintype "unspecified"))
      (node (ref "CN1") (pin "4") (pinfunction "4_4") (pintype "unspecified"))
      (node (ref "LED2") (pin "1") (pinfunction "K_1") (pintype "unspecified"))
      (node (ref "LED3") (pin "1") (pinfunction "K_1") (pintype "unspecified"))
      (node (ref "R12") (pin "1") (pinfunction "1_1") (pintype "input"))
      (node (ref "R14") (pin "2") (pinfunction "2_2") (pintype "input"))
      (node (ref "R15") (pin "1") (pinfunction "1_1") (pintype "input"))
      (node (ref "R16") (pin "2") (pinfunction "2_2") (pintype "input"))
      (node (ref "R25") (pin "1") (pinfunction "1_1") (pintype "input"))
      (node (ref "R3") (pin "1") (pinfunction "1_1") (pintype "input"))
      (node (ref "R9") (pin "1") (pinfunction "1_1") (pintype "input"))
      (node (ref "SW1") (pin "1") (pinfunction "1_1") (pintype "unspecified"))
      (node (ref "SW2") (pin "1") (pinfunction "1_1") (pintype "unspecified"))
      (node (ref "SW3") (pin "2") (pinfunction "2_2") (pintype "unspecified"))
      (node (ref "SW4") (pin "1") (pinfunction "1_1") (pintype "unspecified"))
      (node (ref "SW5") (pin "1") (pinfunction "1_1") (pintype "unspecified"))
      (node (ref "U1") (pin "17") (pinfunction "PGND_17") (pintype "input"))
      (node (ref "U1") (pin "18") (pinfunction "PGND_18") (pintype "input"))
      (node (ref "U1") (pin "25") (pinfunction "PAD_25") (pintype "input"))
      (node (ref "U1") (pin "8") (pinfunction "OTG_8") (pintype "input"))
      (node (ref "U10") (pin "4") (pinfunction "GND_4") (pintype "unspecified"))
      (node (ref "U10") (pin "9") (pinfunction "EP_9") (pintype "unspecified"))
      (node (ref "U11") (pin "10") (pinfunction "SDO2_10") (pintype "unspecified"))
      (node (ref "U11") (pin "15") (pinfunction "SDO1_15") (pintype "unspecified"))
      (node (ref "U11") (pin "2") (pinfunction "NC_2") (pintype "unspecified"))
      (node (ref "U11") (pin "4") (pinfunction "GNDA_4") (pintype "unspecified"))
      (node (ref "U11") (pin "6") (pinfunction "GNDIO_6") (pintype "unspecified"))
      (node (ref "U12") (pin "2") (pinfunction "GND_2") (pintype "input"))
      (node (ref "U12") (pin "4") (pinfunction "GND_4") (pintype "input"))
      (node (ref "U14") (pin "5") (pinfunction "GND_5") (pintype "unspecified"))
      (node (ref "U14") (pin "6") (pinfunction "OE#_6") (pintype "unspecified"))
      (node (ref "U15") (pin "1") (pinfunction "GND_1") (pintype "unspecified"))
      (node (ref "U15") (pin "2") (pinfunction "GND_2") (pintype "unspecified"))
      (node (ref "U15") (pin "36") (pinfunction "GND_36") (pintype "unspecified"))
      (node (ref "U15") (pin "37") (pinfunction "GND_37") (pintype "unspecified"))
      (node (ref "U15") (pin "38") (pinfunction "GND_38") (pintype "unspecified"))
      (node (ref "U15") (pin "39") (pinfunction "GND_39") (pintype "unspecified"))
      (node (ref "U15") (pin "40") (pinfunction "GND_40") (pintype "unspecified"))
      (node (ref "U15") (pin "41") (pinfunction "GND_41") (pintype "unspecified"))
      (node (ref "U15") (pin "42") (pinfunction "GND_42") (pintype "unspecified"))
      (node (ref "U15") (pin "43") (pinfunction "GND_43") (pintype "unspecified"))
      (node (ref "U15") (pin "44") (pinfunction "GND_44") (pintype "unspecified"))
      (node (ref "U15") (pin "45") (pinfunction "GND_45") (pintype "unspecified"))
      (node (ref "U15") (pin "46") (pinfunction "GND_46") (pintype "unspecified"))
      (node (ref "U15") (pin "47") (pinfunction "GND_47") (pintype "unspecified"))
      (node (ref "U15") (pin "48") (pinfunction "GND_48") (pintype "unspecified"))
      (node (ref "U15") (pin "49") (pinfunction "GND_49") (pintype "unspecified"))
      (node (ref "U15") (pin "50") (pinfunction "GND_50") (pintype "unspecified"))
      (node (ref "U15") (pin "51") (pinfunction "GND_51") (pintype "unspecified"))
      (node (ref "U15") (pin "52") (pinfunction "GND_52") (pintype "unspecified"))
      (node (ref "U15") (pin "53") (pinfunction "GND_53") (pintype "unspecified"))
      (node (ref "U17") (pin "1") (pinfunction "1_1") (pintype "unspecified"))
      (node (ref "U17") (pin "19") (pinfunction "19_19") (pintype "unspecified"))
      (node (ref "U17") (pin "25") (pinfunction "25_25") (pintype "unspecified"))
      (node (ref "U17") (pin "26") (pinfunction "26_26") (pintype "unspecified"))
      (node (ref "U3") (pin "1") (pinfunction "CTG_1") (pintype "unspecified"))
      (node (ref "U3") (pin "4") (pinfunction "GND_4") (pintype "unspecified"))
      (node (ref "U3") (pin "6") (pinfunction "QSTRT_6") (pintype "unspecified"))
      (node (ref "U3") (pin "9") (pinfunction "EP_9") (pintype "unspecified"))
      (node (ref "U4") (pin "6") (pinfunction "MODE_6") (pintype "unspecified"))
      (node (ref "U4") (pin "7") (pinfunction "GND_7") (pintype "unspecified"))
      (node (ref "U5") (pin "2") (pinfunction "GND_2") (pintype "unspecified"))
      (node (ref "U6") (pin "2") (pinfunction "GND_2") (pintype "unspecified"))
      (node (ref "U9") (pin "19") (pinfunction "TESTEN_19") (pintype "unspecified"))
      (node (ref "U9") (pin "57") (pinfunction "GND_57") (pintype "bidirectional"))
      (node (ref "USB1") (pin "1") (pinfunction "SHELL_1") (pintype "unspecified"))
      (node (ref "USB1") (pin "2") (pinfunction "SHELL_2") (pintype "unspecified"))
      (node (ref "USB1") (pin "3") (pinfunction "SHELL_3") (pintype "unspecified"))
      (node (ref "USB1") (pin "4") (pinfunction "SHELL_4") (pintype "unspecified"))
      (node (ref "USB1") (pin "A1B12") (pinfunction "GND_A1B12") (pintype "unspecified"))
      (node (ref "USB1") (pin "B1A12") (pinfunction "GND_B1A12") (pintype "unspecified"))
    )
    (net (code "39") (name "I2C_SCL") (class "Default")
      (node (ref "R17") (pin "1") (pinfunction "1_1") (pintype "input"))
      (node (ref "U1") (pin "5") (pinfunction "SCL_5") (pintype "input"))
      (node (ref "U11") (pin "8") (pinfunction "SCL/SCK_8") (pintype "unspecified"))
      (node (ref "U17") (pin "11") (pinfunction "11_11") (pintype "unspecified"))
      (node (ref "U3") (pin "7") (pinfunction "SCL_7") (pintype "unspecified"))
      (node (ref "U9") (pin "12") (pinfunction "GPIO9_12") (pintype "bidirectional"))
    )
    (net (code "40") (name "I2C_SDA") (class "Default")
      (node (ref "R18") (pin "1") (pinfunction "1_1") (pintype "input"))
      (node (ref "U1") (pin "6") (pinfunction "SDA_6") (pintype "input"))
      (node (ref "U11") (pin "9") (pinfunction "SDA/SDI_9") (pintype "unspecified"))
      (node (ref "U17") (pin "13") (pinfunction "13_13") (pintype "unspecified"))
      (node (ref "U3") (pin "8") (pinfunction "SDA_8") (pintype "unspecified"))
      (node (ref "U9") (pin "11") (pinfunction "GPIO8_11") (pintype "bidirectional"))
    )
    (net (code "41") (name "Net-(C4-Pad2)") (class "Default")
      (node (ref "C4") (pin "2") (pinfunction "2_2") (pintype "input"))
      (node (ref "L1") (pin "1") (pinfunction "1_1") (pintype "unspecified"))
      (node (ref "U1") (pin "19") (pinfunction "SW_19") (pintype "input"))
      (node (ref "U1") (pin "20") (pinfunction "SW_20") (pintype "input"))
    )
    (net (code "42") (name "Net-(C36-Pad2)") (class "Default")
      (node (ref "C36") (pin "2") (pinfunction "2_2") (pintype "input"))
      (node (ref "R24") (pin "2") (pinfunction "2_2") (pintype "input"))
      (node (ref "U12") (pin "3") (pinfunction "3_3") (pintype "input"))
    )
    (net (code "43") (name "Net-(LED1-A)") (class "Default")
      (node (ref "LED1") (pin "2") (pinfunction "A_2") (pintype "unspecified"))
      (node (ref "R1") (pin "2") (pinfunction "2_2") (pintype "input"))
    )
    (net (code "44") (name "Net-(LED2-A)") (class "Default")
      (node (ref "LED2") (pin "2") (pinfunction "A_2") (pintype "unspecified"))
      (node (ref "R32") (pin "2") (pinfunction "2_2") (pintype "input"))
    )
    (net (code "45") (name "Net-(LED3-A)") (class "Default")
      (node (ref "LED3") (pin "2") (pinfunction "A_2") (pintype "unspecified"))
      (node (ref "R33") (pin "2") (pinfunction "2_2") (pintype "input"))
    )
    (net (code "46") (name "Net-(R21-Pad1)") (class "Default")
      (node (ref "R21") (pin "1") (pinfunction "1_1") (pintype "input"))
      (node (ref "SW3") (pin "1") (pinfunction "1_1") (pintype "unspecified"))
    )
    (net (code "47") (name "Net-(U1-BTST)") (class "Default")
      (node (ref "C4") (pin "1") (pinfunction "1_1") (pintype "input"))
      (node (ref "U1") (pin "21") (pinfunction "BTST_21") (pintype "input"))
    )
    (net (code "48") (name "Net-(U1-ILIM)") (class "Default")
      (node (ref "R9") (pin "2") (pinfunction "2_2") (pintype "input"))
      (node (ref "U1") (pin "10") (pinfunction "ILIM_10") (pintype "input"))
    )
    (net (code "49") (name "Net-(U4-FB)") (class "Default")
      (node (ref "R11") (pin "1") (pinfunction "1_1") (pintype "input"))
      (node (ref "R12") (pin "2") (pinfunction "2_2") (pintype "input"))
      (node (ref "U4") (pin "8") (pinfunction "FB_8") (pintype "unspecified"))
    )
    (net (code "50") (name "Net-(U4-LX1)") (class "Default")
      (node (ref "L2") (pin "1") (pinfunction "1_1") (pintype "unspecified"))
      (node (ref "U4") (pin "3") (pinfunction "LX1_3") (pintype "unspecified"))
    )
    (net (code "51") (name "Net-(U4-LX2)") (class "Default")
      (node (ref "L2") (pin "2") (pinfunction "2_2") (pintype "unspecified"))
      (node (ref "U4") (pin "2") (pinfunction "LX2_2") (pintype "unspecified"))
    )
    (net (code "52") (name "Net-(U9-RUN)") (class "Default")
      (node (ref "R23") (pin "1") (pinfunction "1_1") (pintype "input"))
      (node (ref "SW4") (pin "2") (pinfunction "2_2") (pintype "unspecified"))
      (node (ref "U9") (pin "26") (pinfunction "RUN_26") (pintype "input"))
    )
    (net (code "53") (name "Net-(U9-USB_DM)") (class "Default")
      (node (ref "R20") (pin "1") (pinfunction "1_1") (pintype "input"))
      (node (ref "U9") (pin "46") (pinfunction "USB_DM_46") (pintype "bidirectional"))
    )
    (net (code "54") (name "Net-(U9-USB_DP)") (class "Default")
      (node (ref "R19") (pin "1") (pinfunction "1_1") (pintype "input"))
      (node (ref "U9") (pin "47") (pinfunction "USB_DP_47") (pintype "bidirectional"))
    )
    (net (code "55") (name "Net-(U15-IO2)") (class "Default")
      (node (ref "R30") (pin "2") (pinfunction "2_2") (pintype "input"))
      (node (ref "U15") (pin "5") (pinfunction "IO2_5") (pintype "unspecified"))
    )
    (net (code "56") (name "Net-(U15-IO8)") (class "Default")
      (node (ref "R31") (pin "2") (pinfunction "2_2") (pintype "input"))
      (node (ref "U15") (pin "22") (pinfunction "IO8_22") (pintype "unspecified"))
    )
    (net (code "57") (name "Net-(U15-RXD0)") (class "Default")
      (node (ref "R29") (pin "1") (pinfunction "1_1") (pintype "input"))
      (node (ref "U15") (pin "30") (pinfunction "RXD0_30") (pintype "unspecified"))
    )
    (net (code "58") (name "Net-(U15-TXD0)") (class "Default")
      (node (ref "R28") (pin "1") (pinfunction "1_1") (pintype "input"))
      (node (ref "U15") (pin "31") (pinfunction "TXD0_31") (pintype "unspecified"))
    )
    (net (code "59") (name "Net-(USB1-CC1)") (class "Default")
      (node (ref "R16") (pin "1") (pinfunction "1_1") (pintype "input"))
      (node (ref "USB1") (pin "A5") (pinfunction "CC1_A5") (pintype "unspecified"))
    )
    (net (code "60") (name "Net-(USB1-CC2)") (class "Default")
      (node (ref "R14") (pin "1") (pinfunction "1_1") (pintype "input"))
      (node (ref "USB1") (pin "B5") (pinfunction "CC2_B5") (pintype "unspecified"))
    )
    (net (code "61") (name "PMID") (class "Default")
      (node (ref "C10") (pin "2") (pinfunction "2_2") (pintype "unspecified"))
      (node (ref "U1") (pin "23") (pinfunction "PMID_23") (pintype "input"))
    )
    (net (code "62") (name "PWR_BAT") (class "Default")
      (node (ref "C15") (pin "2") (pinfunction "2_2") (pintype "unspecified"))
      (node (ref "C17") (pin "1") (pinfunction "1_1") (pintype "input"))
      (node (ref "C18") (pin "1") (pinfunction "1_1") (pintype "input"))
      (node (ref "C5") (pin "2") (pinfunction "2_2") (pintype "input"))
      (node (ref "C6") (pin "2") (pinfunction "2_2") (pintype "input"))
      (node (ref "L1") (pin "2") (pinfunction "2_2") (pintype "unspecified"))
      (node (ref "R1") (pin "1") (pinfunction "1_1") (pintype "input"))
      (node (ref "U1") (pin "15") (pinfunction "SYS_15") (pintype "input"))
      (node (ref "U1") (pin "16") (pinfunction "SYS_16") (pintype "input"))
      (node (ref "U4") (pin "4") (pinfunction "VIN_4") (pintype "unspecified"))
      (node (ref "U5") (pin "6") (pinfunction "VCC_6") (pintype "unspecified"))
      (node (ref "U6") (pin "1") (pinfunction "VIN_1") (pintype "unspecified"))
    )
    (net (code "63") (name "PW_EN") (class "Default")
      (node (ref "R25") (pin "2") (pinfunction "2_2") (pintype "input"))
      (node (ref "U4") (pin "5") (pinfunction "EN_5") (pintype "unspecified"))
      (node (ref "U5") (pin "5") (pinfunction "OUT_5") (pintype "unspecified"))
      (node (ref "U6") (pin "3") (pinfunction "ON_3") (pintype "unspecified"))
    )
    (net (code "64") (name "QSPI_SCLK") (class "Default")
      (node (ref "U10") (pin "6") (pinfunction "CLK_6") (pintype "unspecified"))
      (node (ref "U9") (pin "52") (pinfunction "QSPI_SCLK_52") (pintype "output"))
    )
    (net (code "65") (name "QSPI_SD0") (class "Default")
      (node (ref "U10") (pin "5") (pinfunction "DI(IO0)_5") (pintype "unspecified"))
      (node (ref "U9") (pin "53") (pinfunction "QSPI_SD0_53") (pintype "bidirectional"))
    )
    (net (code "66") (name "QSPI_SD1") (class "Default")
      (node (ref "U10") (pin "2") (pinfunction "DO(IO1)_2") (pintype "unspecified"))
      (node (ref "U9") (pin "55") (pinfunction "QSPI_SD1_55") (pintype "bidirectional"))
    )
    (net (code "67") (name "QSPI_SD2") (class "Default")
      (node (ref "U10") (pin "3") (pinfunction "IO2_3") (pintype "unspecified"))
      (node (ref "U9") (pin "54") (pinfunction "QSPI_SD2_54") (pintype "bidirectional"))
    )
    (net (code "68") (name "QSPI_SD3") (class "Default")
      (node (ref "U10") (pin "7") (pinfunction "IO3_7") (pintype "unspecified"))
      (node (ref "U9") (pin "51") (pinfunction "QSPI_SD3_51") (pintype "bidirectional"))
    )
    (net (code "69") (name "QSPI_SS") (class "Default")
      (node (ref "R21") (pin "2") (pinfunction "2_2") (pintype "input"))
      (node (ref "R22") (pin "2") (pinfunction "2_2") (pintype "input"))
      (node (ref "U10") (pin "1") (pinfunction "CS#_1") (pintype "unspecified"))
      (node (ref "U9") (pin "56") (pinfunction "QSPI_SS_56") (pintype "bidirectional"))
    )
    (net (code "70") (name "REGN") (class "Default")
      (node (ref "C1") (pin "2") (pinfunction "2_2") (pintype "unspecified"))
      (node (ref "R2") (pin "2") (pinfunction "2_2") (pintype "input"))
      (node (ref "U1") (pin "22") (pinfunction "REGN_22") (pintype "input"))
    )
    (net (code "71") (name "RP_D2+") (class "Default")
      (node (ref "R19") (pin "2") (pinfunction "2_2") (pintype "input"))
      (node (ref "U14") (pin "3") (pinfunction "2D+_3") (pintype "unspecified"))
    )
    (net (code "72") (name "RP_D2-") (class "Default")
      (node (ref "R20") (pin "2") (pinfunction "2_2") (pintype "input"))
      (node (ref "U14") (pin "4") (pinfunction "2D-_4") (pintype "unspecified"))
    )
    (net (code "73") (name "RP_LED") (class "Default")
      (node (ref "R33") (pin "1") (pinfunction "1_1") (pintype "input"))
      (node (ref "U9") (pin "28") (pinfunction "GPIO17_28") (pintype "bidirectional"))
    )
    (net (code "74") (name "RX_RP") (class "Default")
      (node (ref "R28") (pin "2") (pinfunction "2_2") (pintype "input"))
      (node (ref "U17") (pin "17") (pinfunction "17_17") (pintype "unspecified"))
      (node (ref "U9") (pin "7") (pinfunction "GPIO5_7") (pintype "bidirectional"))
    )
    (net (code "75") (name "STAT") (class "Default")
      (node (ref "LED1") (pin "1") (pinfunction "K_1") (pintype "unspecified"))
      (node (ref "U1") (pin "4") (pinfunction "STAT_4") (pintype "input"))
    )
    (net (code "76") (name "TS") (class "Default")
      (node (ref "R2") (pin "1") (pinfunction "1_1") (pintype "input"))
      (node (ref "R3") (pin "2") (pinfunction "2_2") (pintype "input"))
      (node (ref "U1") (pin "11") (pinfunction "TS_11") (pintype "input"))
    )
    (net (code "77") (name "TX_RP") (class "Default")
      (node (ref "R29") (pin "2") (pinfunction "2_2") (pintype "input"))
      (node (ref "U17") (pin "15") (pinfunction "15_15") (pintype "unspecified"))
      (node (ref "U9") (pin "6") (pinfunction "GPIO4_6") (pintype "bidirectional"))
    )
    (net (code "78") (name "USB_SEL") (class "Default")
      (node (ref "R13") (pin "2") (pinfunction "2_2") (pintype "input"))
      (node (ref "U1") (pin "24") (pinfunction "DSEL_24") (pintype "input"))
      (node (ref "U14") (pin "9") (pinfunction "S_9") (pintype "unspecified"))
    )
    (net (code "79") (name "VUSB") (class "Default")
      (node (ref "C19") (pin "2") (pinfunction "2_2") (pintype "unspecified"))
      (node (ref "C9") (pin "2") (pinfunction "2_2") (pintype "unspecified"))
      (node (ref "R13") (pin "1") (pinfunction "1_1") (pintype "input"))
      (node (ref "U1") (pin "1") (pinfunction "VBUS_1") (pintype "input"))
      (node (ref "U14") (pin "10") (pinfunction "VCC_10") (pintype "unspecified"))
      (node (ref "U17") (pin "30") (pinfunction "30_30") (pintype "unspecified"))
      (node (ref "USB1") (pin "A4B9") (pinfunction "VBUS_A4B9") (pintype "unspecified"))
      (node (ref "USB1") (pin "B4A9") (pinfunction "VBUS_B4A9") (pintype "unspecified"))
    )
    (net (code "80") (name "unconnected-(U1-QON-Pad12)") (class "Default")
      (node (ref "U1") (pin "12") (pinfunction "QON_12") (pintype "input+no_connect"))
    )
    (net (code "81") (name "unconnected-(U3-ALRT#-Pad5)") (class "Default")
      (node (ref "U3") (pin "5") (pinfunction "ALRT#_5") (pintype "unspecified+no_connect"))
    )
    (net (code "82") (name "unconnected-(U5-#OUT-Pad4)") (class "Default")
      (node (ref "U5") (pin "4") (pinfunction "#OUT_4") (pintype "unspecified+no_connect"))
    )
    (net (code "83") (name "unconnected-(U6-CT-Pad4)") (class "Default")
      (node (ref "U6") (pin "4") (pinfunction "CT_4") (pintype "unspecified+no_connect"))
    )
    (net (code "84") (name "unconnected-(U6-QOD-Pad5)") (class "Default")
      (node (ref "U6") (pin "5") (pinfunction "QOD_5") (pintype "unspecified+no_connect"))
    )
    (net (code "85") (name "unconnected-(U9-GPIO12-Pad15)") (class "Default")
      (node (ref "U9") (pin "15") (pinfunction "GPIO12_15") (pintype "bidirectional+no_connect"))
    )
    (net (code "86") (name "unconnected-(U9-GPIO13-Pad16)") (class "Default")
      (node (ref "U9") (pin "16") (pinfunction "GPIO13_16") (pintype "bidirectional+no_connect"))
    )
    (net (code "87") (name "unconnected-(U9-GPIO14-Pad17)") (class "Default")
      (node (ref "U9") (pin "17") (pinfunction "GPIO14_17") (pintype "bidirectional+no_connect"))
    )
    (net (code "88") (name "unconnected-(U9-GPIO15-Pad18)") (class "Default")
      (node (ref "U9") (pin "18") (pinfunction "GPIO15_18") (pintype "bidirectional+no_connect"))
    )
    (net (code "89") (name "unconnected-(U9-GPIO16-Pad27)") (class "Default")
      (node (ref "U9") (pin "27") (pinfunction "GPIO16_27") (pintype "bidirectional+no_connect"))
    )
    (net (code "90") (name "unconnected-(U9-SWCLK-Pad24)") (class "Default")
      (node (ref "U9") (pin "24") (pinfunction "SWCLK_24") (pintype "output+no_connect"))
    )
    (net (code "91") (name "unconnected-(U9-SWD-Pad25)") (class "Default")
      (node (ref "U9") (pin "25") (pinfunction "SWD_25") (pintype "bidirectional+no_connect"))
    )
    (net (code "92") (name "unconnected-(U11-CSB2-Pad5)") (class "Default")
      (node (ref "U11") (pin "5") (pinfunction "CSB2_5") (pintype "unspecified+no_connect"))
    )
    (net (code "93") (name "unconnected-(U11-INT2-Pad1)") (class "Default")
      (node (ref "U11") (pin "1") (pinfunction "INT2_1") (pintype "unspecified+no_connect"))
    )
    (net (code "94") (name "unconnected-(U11-INT4-Pad13)") (class "Default")
      (node (ref "U11") (pin "13") (pinfunction "INT4_13") (pintype "unspecified+no_connect"))
    )
    (net (code "95") (name "unconnected-(U15-GND-Pad11)") (class "Default")
      (node (ref "U15") (pin "11") (pinfunction "GND_11") (pintype "unspecified+no_connect"))
    )
    (net (code "96") (name "unconnected-(U15-GND-Pad14)") (class "Default")
      (node (ref "U15") (pin "14") (pinfunction "GND_14") (pintype "unspecified+no_connect"))
    )
    (net (code "97") (name "unconnected-(U15-IO0-Pad12)") (class "Default")
      (node (ref "U15") (pin "12") (pinfunction "IO0_12") (pintype "unspecified+no_connect"))
    )
    (net (code "98") (name "unconnected-(U15-IO3-Pad6)") (class "Default")
      (node (ref "U15") (pin "6") (pinfunction "IO3_6") (pintype "unspecified+no_connect"))
    )
    (net (code "99") (name "unconnected-(U15-IO10-Pad16)") (class "Default")
      (node (ref "U15") (pin "16") (pinfunction "IO10_16") (pintype "unspecified+no_connect"))
    )
    (net (code "100") (name "unconnected-(U15-IO18-Pad26)") (class "Default")
      (node (ref "U15") (pin "26") (pinfunction "IO18_26") (pintype "unspecified+no_connect"))
    )
    (net (code "101") (name "unconnected-(U15-IO19-Pad27)") (class "Default")
      (node (ref "U15") (pin "27") (pinfunction "IO19_27") (pintype "unspecified+no_connect"))
    )
    (net (code "102") (name "unconnected-(U15-NC-Pad4)") (class "Default")
      (node (ref "U15") (pin "4") (pinfunction "NC_4") (pintype "unspecified+no_connect"))
    )
    (net (code "103") (name "unconnected-(U15-NC-Pad7)") (class "Default")
      (node (ref "U15") (pin "7") (pinfunction "NC_7") (pintype "unspecified+no_connect"))
    )
    (net (code "104") (name "unconnected-(U15-NC-Pad9)") (class "Default")
      (node (ref "U15") (pin "9") (pinfunction "NC_9") (pintype "unspecified+no_connect"))
    )
    (net (code "105") (name "unconnected-(U15-NC-Pad10)") (class "Default")
      (node (ref "U15") (pin "10") (pinfunction "NC_10") (pintype "unspecified+no_connect"))
    )
    (net (code "106") (name "unconnected-(U15-NC-Pad15)") (class "Default")
      (node (ref "U15") (pin "15") (pinfunction "NC_15") (pintype "unspecified+no_connect"))
    )
    (net (code "107") (name "unconnected-(U15-NC-Pad17)") (class "Default")
      (node (ref "U15") (pin "17") (pinfunction "NC_17") (pintype "unspecified+no_connect"))
    )
    (net (code "108") (name "unconnected-(U15-NC-Pad24)") (class "Default")
      (node (ref "U15") (pin "24") (pinfunction "NC_24") (pintype "unspecified+no_connect"))
    )
    (net (code "109") (name "unconnected-(U15-NC-Pad25)") (class "Default")
      (node (ref "U15") (pin "25") (pinfunction "NC_25") (pintype "unspecified+no_connect"))
    )
    (net (code "110") (name "unconnected-(U15-NC-Pad28)") (class "Default")
      (node (ref "U15") (pin "28") (pinfunction "NC_28") (pintype "unspecified+no_connect"))
    )
    (net (code "111") (name "unconnected-(U15-NC-Pad29)") (class "Default")
      (node (ref "U15") (pin "29") (pinfunction "NC_29") (pintype "unspecified+no_connect"))
    )
    (net (code "112") (name "unconnected-(U15-NC-Pad32)") (class "Default")
      (node (ref "U15") (pin "32") (pinfunction "NC_32") (pintype "unspecified+no_connect"))
    )
    (net (code "113") (name "unconnected-(U15-NC-Pad33)") (class "Default")
      (node (ref "U15") (pin "33") (pinfunction "NC_33") (pintype "unspecified+no_connect"))
    )
    (net (code "114") (name "unconnected-(U15-NC-Pad34)") (class "Default")
      (node (ref "U15") (pin "34") (pinfunction "NC_34") (pintype "unspecified+no_connect"))
    )
    (net (code "115") (name "unconnected-(U15-NC-Pad35)") (class "Default")
      (node (ref "U15") (pin "35") (pinfunction "NC_35") (pintype "unspecified+no_connect"))
    )
    (net (code "116") (name "unconnected-(USB1-SBU1-PadA8)") (class "Default")
      (node (ref "USB1") (pin "A8") (pinfunction "SBU1_A8") (pintype "unspecified+no_connect"))
    )
    (net (code "117") (name "unconnected-(USB1-SBU2-PadB8)") (class "Default")
      (node (ref "USB1") (pin "B8") (pinfunction "SBU2_B8") (pintype "unspecified+no_connect"))
    )
  )
)
